# ActiTouch_Shield_Sheet1.net
KiCad netlist of a schematic drawn in Altium Designer
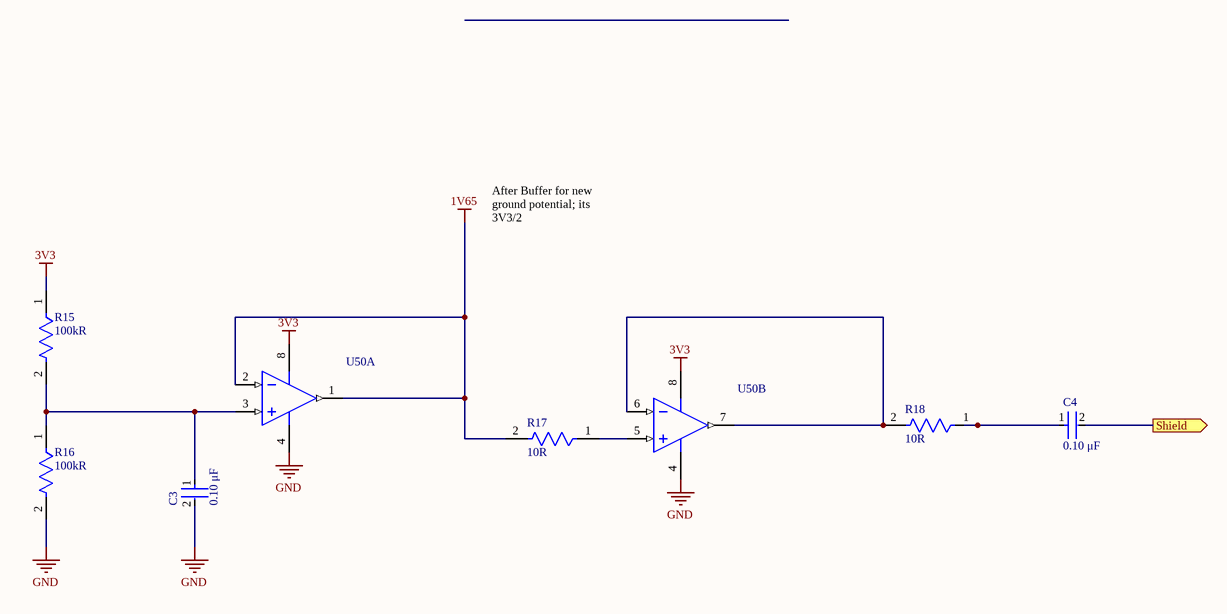
[diagram p0: ActiTouch_Shield_Sheet1.SchDoc]

(export (version "E")
  (design (tool "Eeschema 10.0.6"))
  (components
    (comp (ref "C3")
      (value "0.10 μF")
      (footprint "FP-C0603C-CF-MFG")
      (description "CAP CER 0.1UF 50V X7R 0603")
      (fields (field (name "TOLERANCE") "0.1") (field (name "MANUFACTURER") "KEMET"))
      (libsource (lib "Altium Content Vault") (part "b4654b650e69147ec39a6b967a45e02"))
    )
    (comp (ref "C4")
      (value "0.10 μF")
      (footprint "FP-C0603C-CF-MFG")
      (description "CAP CER 0.1UF 50V X7R 0603")
      (fields (field (name "TOLERANCE") "0.1") (field (name "MANUFACTURER") "KEMET"))
      (libsource (lib "Altium Content Vault") (part "b4654b650e69147ec39a6b967a45e02"))
    )
    (comp (ref "R15")
      (value "ESR03EZPJ101")
      (footprint "FP-ESR03-MFG")
      (description "100Ω ±5% 0.25W 0603 Anti-Surge Chip Resistor AEC-Q200")
      (fields (field (name "TOLERANCE") "5%") (field (name "RESISTANCE") "100kR"))
      (libsource (lib "Altium Content Vault") (part "1029c3af85768c4190bb7ad29bc67b5"))
    )
    (comp (ref "R16")
      (value "ESR03EZPJ101")
      (footprint "FP-ESR03-MFG")
      (description "100Ω ±5% 0.25W 0603 Anti-Surge Chip Resistor AEC-Q200")
      (fields (field (name "TOLERANCE") "5%") (field (name "RESISTANCE") "100kR"))
      (libsource (lib "Altium Content Vault") (part "1029c3af85768c4190bb7ad29bc67b5"))
    )
    (comp (ref "R17")
      (value "ESR03EZPJ101")
      (footprint "FP-ESR03-MFG")
      (description "100Ω ±5% 0.25W 0603 Anti-Surge Chip Resistor AEC-Q200")
      (fields (field (name "TOLERANCE") "5%") (field (name "RESISTANCE") "10R"))
      (libsource (lib "Altium Content Vault") (part "1029c3af85768c4190bb7ad29bc67b5"))
    )
    (comp (ref "R18")
      (value "ESR03EZPJ101")
      (footprint "FP-ESR03-MFG")
      (description "100Ω ±5% 0.25W 0603 Anti-Surge Chip Resistor AEC-Q200")
      (fields (field (name "TOLERANCE") "5%") (field (name "RESISTANCE") "10R"))
      (libsource (lib "Altium Content Vault") (part "1029c3af85768c4190bb7ad29bc67b5"))
    )
    (comp (ref "U50")
      (value "LTC6253IMS8#TRPBF")
      (footprint "LT-MS8-8_M")
      (fields
        (field (name "LINEAR TECHNOLOGY PART NUMBER") "LTC6253")
        (field (name "MANUFACTURER") "Linear Technology")
      )
      (libsource (lib "Altium Content Vault") (part "LT-LTC6253-MS8-8"))
    )
  )
  (nets
    (net (code "1") (name "/Shield") (class "Default")
      (node (ref "C4") (pin "2") (pinfunction "2_2") (pintype "passive"))
    )
    (net (code "2") (name "1V65") (class "Default")
      (node (ref "R17") (pin "2") (pinfunction "2_2") (pintype "passive"))
      (node (ref "U50") (pin "1") (pinfunction "OUT_A_1") (pintype "output"))
      (node (ref "U50") (pin "2") (pinfunction "-IN_A_2") (pintype "input"))
    )
    (net (code "3") (name "3V3") (class "Default")
      (node (ref "R15") (pin "1") (pinfunction "1_1") (pintype "passive"))
      (node (ref "U50") (pin "8") (pinfunction "V+_8") (pintype "power_in"))
    )
    (net (code "4") (name "GND") (class "Default")
      (node (ref "C3") (pin "2") (pinfunction "2_2") (pintype "passive"))
      (node (ref "R16") (pin "2") (pinfunction "2_2") (pintype "passive"))
      (node (ref "U50") (pin "4") (pinfunction "V-_4") (pintype "power_in"))
    )
    (net (code "5") (name "Net-(C4-Pad1)") (class "Default")
      (node (ref "C4") (pin "1") (pinfunction "1_1") (pintype "passive"))
      (node (ref "R18") (pin "1") (pinfunction "1_1") (pintype "passive"))
    )
    (net (code "6") (name "Net-(U50A-+IN_A)") (class "Default")
      (node (ref "C3") (pin "1") (pinfunction "1_1") (pintype "passive"))
      (node (ref "R15") (pin "2") (pinfunction "2_2") (pintype "passive"))
      (node (ref "R16") (pin "1") (pinfunction "1_1") (pintype "passive"))
      (node (ref "U50") (pin "3") (pinfunction "+IN_A_3") (pintype "input"))
    )
    (net (code "7") (name "Net-(U50B-+IN_B)") (class "Default")
      (node (ref "R17") (pin "1") (pinfunction "1_1") (pintype "passive"))
      (node (ref "U50") (pin "5") (pinfunction "+IN_B_5") (pintype "input"))
    )
    (net (code "8") (name "Net-(U50B--IN_B)") (class "Default")
      (node (ref "R18") (pin "2") (pinfunction "2_2") (pintype "passive"))
      (node (ref "U50") (pin "6") (pinfunction "-IN_B_6") (pintype "input"))
      (node (ref "U50") (pin "7") (pinfunction "OUT_B_7") (pintype "output"))
    )
  )
)
